# refletancia.net
KiCad netlist of a schematic drawn in EAGLE
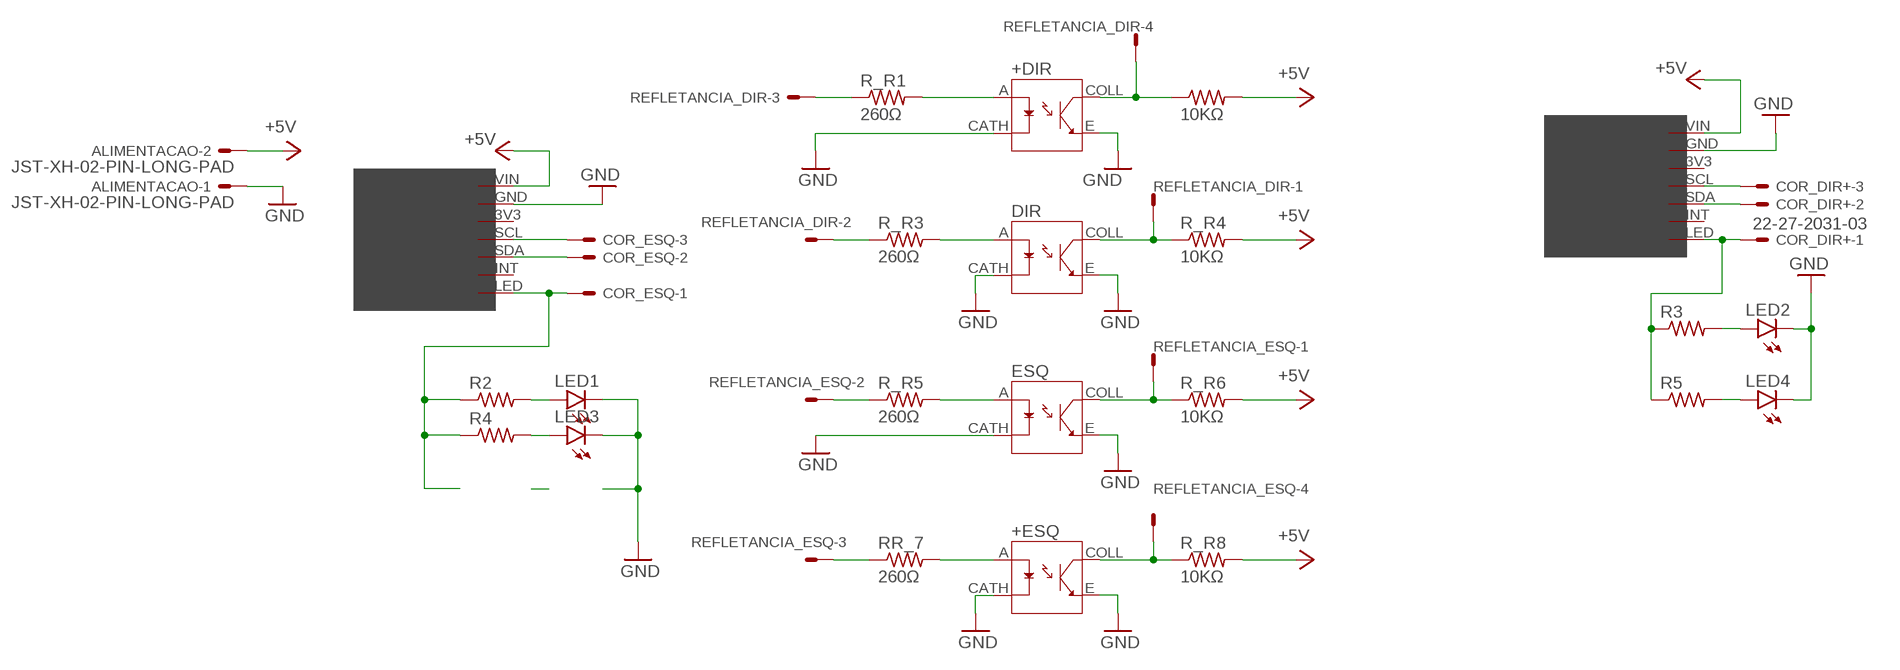
[diagram p0: schematic, sheet 1]

(export (version "E")
  (design (tool "Eeschema 10.0.6"))
  (components
    (comp (ref "+DIR")
      (value "TCRT5000")
      (footprint "eagle-import:OPTO_TCRT5000")
      (fields (field (name "MF") "Vishay"))
      (libsource (lib "eagle-import") (part "TCRT5000"))
    )
    (comp (ref "+ESQ")
      (value "TCRT5000")
      (footprint "eagle-import:OPTO_TCRT5000")
      (fields (field (name "MF") "Vishay"))
      (libsource (lib "eagle-import") (part "TCRT5000"))
    )
    (comp (ref "ALIMENTACAO")
      (value "JST-XH-02-PIN-LONG-PAD")
      (footprint "eagle-import:JST-XH-02-PACKAGE-LONG-PAD")
      (libsource (lib "eagle-import") (part "JST-XH-02-PIN-LONG-PAD"))
    )
    (comp (ref "COR_DIR+")
      (value "22-27-2031-03")
      (footprint "eagle-import:6410-03")
      (fields (field (name "MF") "MOLEX"))
      (libsource (lib "eagle-import") (part "22-?-0327-2031"))
    )
    (comp (ref "COR_ESQ")
      (value "22-27-2031-03")
      (footprint "eagle-import:6410-03")
      (fields (field (name "MF") "MOLEX"))
      (libsource (lib "eagle-import") (part "22-?-0327-2031"))
    )
    (comp (ref "DIR")
      (value "TCRT5000")
      (footprint "eagle-import:OPTO_TCRT5000")
      (fields (field (name "MF") "Vishay"))
      (libsource (lib "eagle-import") (part "TCRT5000"))
    )
    (comp (ref "ESQ")
      (value "TCRT5000")
      (footprint "eagle-import:OPTO_TCRT5000")
      (fields (field (name "MF") "Vishay"))
      (libsource (lib "eagle-import") (part "TCRT5000"))
    )
    (comp (ref "LED1")
      (value "LED5MM")
      (footprint "eagle-import:LED5MM")
      (libsource (lib "eagle-import") (part "led_robotica_LED5MM"))
    )
    (comp (ref "LED2")
      (value "LED5MM")
      (footprint "eagle-import:LED5MM")
      (libsource (lib "eagle-import") (part "led_robotica_LED5MM"))
    )
    (comp (ref "LED3")
      (value "LEDCHIP-LED0805")
      (footprint "eagle-import:CHIP-LED0805")
      (libsource (lib "eagle-import") (part "LEDCHIP-LED0805"))
    )
    (comp (ref "LED4")
      (value "LEDCHIP-LED0805")
      (footprint "eagle-import:CHIP-LED0805")
      (libsource (lib "eagle-import") (part "LEDCHIP-LED0805"))
    )
    (comp (ref "R2")
      (value "R-US_0204/7")
      (footprint "eagle-import:0204_7")
      (libsource (lib "eagle-import") (part "R-US_0204/7"))
    )
    (comp (ref "R3")
      (value "R-US_0204/7")
      (footprint "eagle-import:0204_7")
      (libsource (lib "eagle-import") (part "R-US_0204/7"))
    )
    (comp (ref "R4")
      (value "R-US_0204/7")
      (footprint "eagle-import:0204_7")
      (libsource (lib "eagle-import") (part "R-US_0204/7"))
    )
    (comp (ref "R5")
      (value "R-US_0204/7")
      (footprint "eagle-import:0204_7")
      (libsource (lib "eagle-import") (part "R-US_0204/7"))
    )
    (comp (ref "REFLETANCIA_DIR")
      (value "JST-XH-04-PIN-LONG-PAD")
      (footprint "eagle-import:JST-XH-04-PACKAGE-LONG-PAD")
      (libsource (lib "eagle-import") (part "JST-XH-04-PIN-LONG-PAD"))
    )
    (comp (ref "REFLETANCIA_ESQ")
      (value "JST-XH-04-PIN-LONG-PAD")
      (footprint "eagle-import:JST-XH-04-PACKAGE-LONG-PAD")
      (libsource (lib "eagle-import") (part "JST-XH-04-PIN-LONG-PAD"))
    )
    (comp (ref "RR_7")
      (value "260Ω")
      (footprint "eagle-import:0204_7")
      (libsource (lib "eagle-import") (part "R-US_0204/7"))
    )
    (comp (ref "R_R1")
      (value "260Ω")
      (footprint "eagle-import:0204_7")
      (libsource (lib "eagle-import") (part "R-US_0204/7"))
    )
    (comp (ref "R_R2")
      (value "10KΩ")
      (footprint "eagle-import:0204_7")
      (libsource (lib "eagle-import") (part "R-US_0204/7"))
    )
    (comp (ref "R_R3")
      (value "260Ω")
      (footprint "eagle-import:0414_15_LOG_PAD")
      (libsource (lib "eagle-import") (part "R-US_0414/15_LONG_PAD"))
    )
    (comp (ref "R_R4")
      (value "10KΩ")
      (footprint "eagle-import:0204_7")
      (libsource (lib "eagle-import") (part "R-US_0204/7"))
    )
    (comp (ref "R_R5")
      (value "260Ω")
      (footprint "eagle-import:0204_7")
      (libsource (lib "eagle-import") (part "R-US_0204/7"))
    )
    (comp (ref "R_R6")
      (value "10KΩ")
      (footprint "eagle-import:0207_7_LONG_PAD2")
      (libsource (lib "eagle-import") (part "R-US_0207/7_LONG_PAD2"))
    )
    (comp (ref "R_R8")
      (value "10KΩ")
      (footprint "eagle-import:0204_7")
      (libsource (lib "eagle-import") (part "R-US_0204/7"))
    )
    (comp (ref "U$1")
      (value "TCS34725SEM_FUROS")
      (footprint "eagle-import:TCS34725_SEM_FUROS")
      (libsource (lib "eagle-import") (part "TCS34725SEM_FUROS"))
    )
    (comp (ref "U$2")
      (value "TCS34725SEM_FUROS")
      (footprint "eagle-import:TCS34725_SEM_FUROS")
      (libsource (lib "eagle-import") (part "TCS34725SEM_FUROS"))
    )
  )
  (nets
    (net (code "1") (name "+5V") (class "Default")
      (node (ref "ALIMENTACAO") (pin "2") (pinfunction "S_2") (pintype "passive"))
      (node (ref "R_R2") (pin "2") (pinfunction "2_2") (pintype "passive"))
      (node (ref "R_R4") (pin "2") (pinfunction "2_2") (pintype "passive"))
      (node (ref "R_R6") (pin "2") (pinfunction "2_2") (pintype "passive"))
      (node (ref "R_R8") (pin "2") (pinfunction "2_2") (pintype "passive"))
      (node (ref "U$1") (pin "VIN") (pinfunction "VIN_VIN") (pintype "bidirectional"))
      (node (ref "U$2") (pin "VIN") (pinfunction "VIN_VIN") (pintype "bidirectional"))
    )
    (net (code "2") (name "GND") (class "Default")
      (node (ref "+DIR") (pin "CATH") (pinfunction "CATH_CATH") (pintype "passive"))
      (node (ref "+DIR") (pin "E") (pinfunction "E_E") (pintype "passive"))
      (node (ref "+ESQ") (pin "CATH") (pinfunction "CATH_CATH") (pintype "passive"))
      (node (ref "+ESQ") (pin "E") (pinfunction "E_E") (pintype "passive"))
      (node (ref "ALIMENTACAO") (pin "1") (pinfunction "S_1") (pintype "passive"))
      (node (ref "DIR") (pin "CATH") (pinfunction "CATH_CATH") (pintype "passive"))
      (node (ref "DIR") (pin "E") (pinfunction "E_E") (pintype "passive"))
      (node (ref "ESQ") (pin "CATH") (pinfunction "CATH_CATH") (pintype "passive"))
      (node (ref "ESQ") (pin "E") (pinfunction "E_E") (pintype "passive"))
      (node (ref "LED1") (pin "K") (pinfunction "C_K") (pintype "passive"))
      (node (ref "LED2") (pin "K") (pinfunction "C_K") (pintype "passive"))
      (node (ref "LED3") (pin "C") (pinfunction "C_C") (pintype "passive"))
      (node (ref "LED4") (pin "C") (pinfunction "C_C") (pintype "passive"))
      (node (ref "U$1") (pin "GND") (pinfunction "GND_GND") (pintype "bidirectional"))
      (node (ref "U$2") (pin "GND") (pinfunction "GND_GND") (pintype "bidirectional"))
    )
    (net (code "3") (name "Net-(+DIR-PadA)") (class "Default")
      (node (ref "+DIR") (pin "A") (pinfunction "A_A") (pintype "passive"))
      (node (ref "R_R1") (pin "2") (pinfunction "2_2") (pintype "passive"))
    )
    (net (code "4") (name "Net-(+ESQ-PadA)") (class "Default")
      (node (ref "+ESQ") (pin "A") (pinfunction "A_A") (pintype "passive"))
      (node (ref "RR_7") (pin "2") (pinfunction "2_2") (pintype "passive"))
    )
    (net (code "5") (name "Net-(COR_DIR+A-S)") (class "Default")
      (node (ref "COR_DIR+") (pin "1") (pinfunction "S_1") (pintype "passive"))
      (node (ref "R3") (pin "1") (pinfunction "1_1") (pintype "passive"))
      (node (ref "R5") (pin "1") (pinfunction "1_1") (pintype "passive"))
      (node (ref "U$2") (pin "LED") (pinfunction "LED_LED") (pintype "bidirectional"))
    )
    (net (code "6") (name "Net-(COR_DIR+B-S)") (class "Default")
      (node (ref "COR_DIR+") (pin "2") (pinfunction "S_2") (pintype "passive"))
      (node (ref "U$2") (pin "SDA") (pinfunction "SDA_SDA") (pintype "bidirectional"))
    )
    (net (code "7") (name "Net-(COR_DIR+C-S)") (class "Default")
      (node (ref "COR_DIR+") (pin "3") (pinfunction "S_3") (pintype "passive"))
      (node (ref "U$2") (pin "SCL") (pinfunction "SCL_SCL") (pintype "bidirectional"))
    )
    (net (code "8") (name "Net-(COR_ESQA-S)") (class "Default")
      (node (ref "COR_ESQ") (pin "1") (pinfunction "S_1") (pintype "passive"))
      (node (ref "R2") (pin "1") (pinfunction "1_1") (pintype "passive"))
      (node (ref "R4") (pin "1") (pinfunction "1_1") (pintype "passive"))
      (node (ref "U$1") (pin "LED") (pinfunction "LED_LED") (pintype "bidirectional"))
    )
    (net (code "9") (name "Net-(COR_ESQB-S)") (class "Default")
      (node (ref "COR_ESQ") (pin "2") (pinfunction "S_2") (pintype "passive"))
      (node (ref "U$1") (pin "SDA") (pinfunction "SDA_SDA") (pintype "bidirectional"))
    )
    (net (code "10") (name "Net-(COR_ESQC-S)") (class "Default")
      (node (ref "COR_ESQ") (pin "3") (pinfunction "S_3") (pintype "passive"))
      (node (ref "U$1") (pin "SCL") (pinfunction "SCL_SCL") (pintype "bidirectional"))
    )
    (net (code "11") (name "Net-(DIR-PadA)") (class "Default")
      (node (ref "DIR") (pin "A") (pinfunction "A_A") (pintype "passive"))
      (node (ref "R_R3") (pin "2") (pinfunction "2_2") (pintype "passive"))
    )
    (net (code "12") (name "Net-(ESQ-PadA)") (class "Default")
      (node (ref "ESQ") (pin "A") (pinfunction "A_A") (pintype "passive"))
      (node (ref "R_R5") (pin "2") (pinfunction "2_2") (pintype "passive"))
    )
    (net (code "13") (name "Net-(LED1-PadA)") (class "Default")
      (node (ref "LED1") (pin "A") (pinfunction "A_A") (pintype "passive"))
      (node (ref "R2") (pin "2") (pinfunction "2_2") (pintype "passive"))
    )
    (net (code "14") (name "Net-(LED2-PadA)") (class "Default")
      (node (ref "LED2") (pin "A") (pinfunction "A_A") (pintype "passive"))
      (node (ref "R3") (pin "2") (pinfunction "2_2") (pintype "passive"))
    )
    (net (code "15") (name "Net-(LED3-PadA)") (class "Default")
      (node (ref "LED3") (pin "A") (pinfunction "A_A") (pintype "passive"))
      (node (ref "R4") (pin "2") (pinfunction "2_2") (pintype "passive"))
    )
    (net (code "16") (name "Net-(LED4-PadA)") (class "Default")
      (node (ref "LED4") (pin "A") (pinfunction "A_A") (pintype "passive"))
      (node (ref "R5") (pin "2") (pinfunction "2_2") (pintype "passive"))
    )
    (net (code "17") (name "Net-(REFLETANCIA_DIRA-S)") (class "Default")
      (node (ref "DIR") (pin "COLL") (pinfunction "COLL_COLL") (pintype "passive"))
      (node (ref "REFLETANCIA_DIR") (pin "1") (pinfunction "S_1") (pintype "passive"))
      (node (ref "R_R4") (pin "1") (pinfunction "1_1") (pintype "passive"))
    )
    (net (code "18") (name "Net-(REFLETANCIA_DIRB-S)") (class "Default")
      (node (ref "REFLETANCIA_DIR") (pin "2") (pinfunction "S_2") (pintype "passive"))
      (node (ref "R_R3") (pin "1") (pinfunction "1_1") (pintype "passive"))
    )
    (net (code "19") (name "Net-(REFLETANCIA_DIRC-S)") (class "Default")
      (node (ref "REFLETANCIA_DIR") (pin "3") (pinfunction "S_3") (pintype "passive"))
      (node (ref "R_R1") (pin "1") (pinfunction "1_1") (pintype "passive"))
    )
    (net (code "20") (name "Net-(REFLETANCIA_DIRD-S)") (class "Default")
      (node (ref "+DIR") (pin "COLL") (pinfunction "COLL_COLL") (pintype "passive"))
      (node (ref "REFLETANCIA_DIR") (pin "4") (pinfunction "S_4") (pintype "passive"))
      (node (ref "R_R2") (pin "1") (pinfunction "1_1") (pintype "passive"))
    )
    (net (code "21") (name "Net-(REFLETANCIA_ESQA-S)") (class "Default")
      (node (ref "ESQ") (pin "COLL") (pinfunction "COLL_COLL") (pintype "passive"))
      (node (ref "REFLETANCIA_ESQ") (pin "1") (pinfunction "S_1") (pintype "passive"))
      (node (ref "R_R6") (pin "1") (pinfunction "1_1") (pintype "passive"))
    )
    (net (code "22") (name "Net-(REFLETANCIA_ESQB-S)") (class "Default")
      (node (ref "REFLETANCIA_ESQ") (pin "2") (pinfunction "S_2") (pintype "passive"))
      (node (ref "R_R5") (pin "1") (pinfunction "1_1") (pintype "passive"))
    )
    (net (code "23") (name "Net-(REFLETANCIA_ESQC-S)") (class "Default")
      (node (ref "REFLETANCIA_ESQ") (pin "3") (pinfunction "S_3") (pintype "passive"))
      (node (ref "RR_7") (pin "1") (pinfunction "1_1") (pintype "passive"))
    )
    (net (code "24") (name "Net-(REFLETANCIA_ESQD-S)") (class "Default")
      (node (ref "+ESQ") (pin "COLL") (pinfunction "COLL_COLL") (pintype "passive"))
      (node (ref "REFLETANCIA_ESQ") (pin "4") (pinfunction "S_4") (pintype "passive"))
      (node (ref "R_R8") (pin "1") (pinfunction "1_1") (pintype "passive"))
    )
    (net (code "25") (name "unconnected-(U$1-Pad3V3)") (class "Default")
      (node (ref "U$1") (pin "3V3") (pinfunction "3V3_3V3") (pintype "bidirectional"))
    )
    (net (code "26") (name "unconnected-(U$1-PadINT)") (class "Default")
      (node (ref "U$1") (pin "INT") (pinfunction "INT_INT") (pintype "bidirectional"))
    )
    (net (code "27") (name "unconnected-(U$2-Pad3V3)") (class "Default")
      (node (ref "U$2") (pin "3V3") (pinfunction "3V3_3V3") (pintype "bidirectional"))
    )
    (net (code "28") (name "unconnected-(U$2-PadINT)") (class "Default")
      (node (ref "U$2") (pin "INT") (pinfunction "INT_INT") (pintype "bidirectional"))
    )
  )
)
